# STRWL-S01-V00-Master.net
KiCad netlist of a schematic drawn in Altium Designer
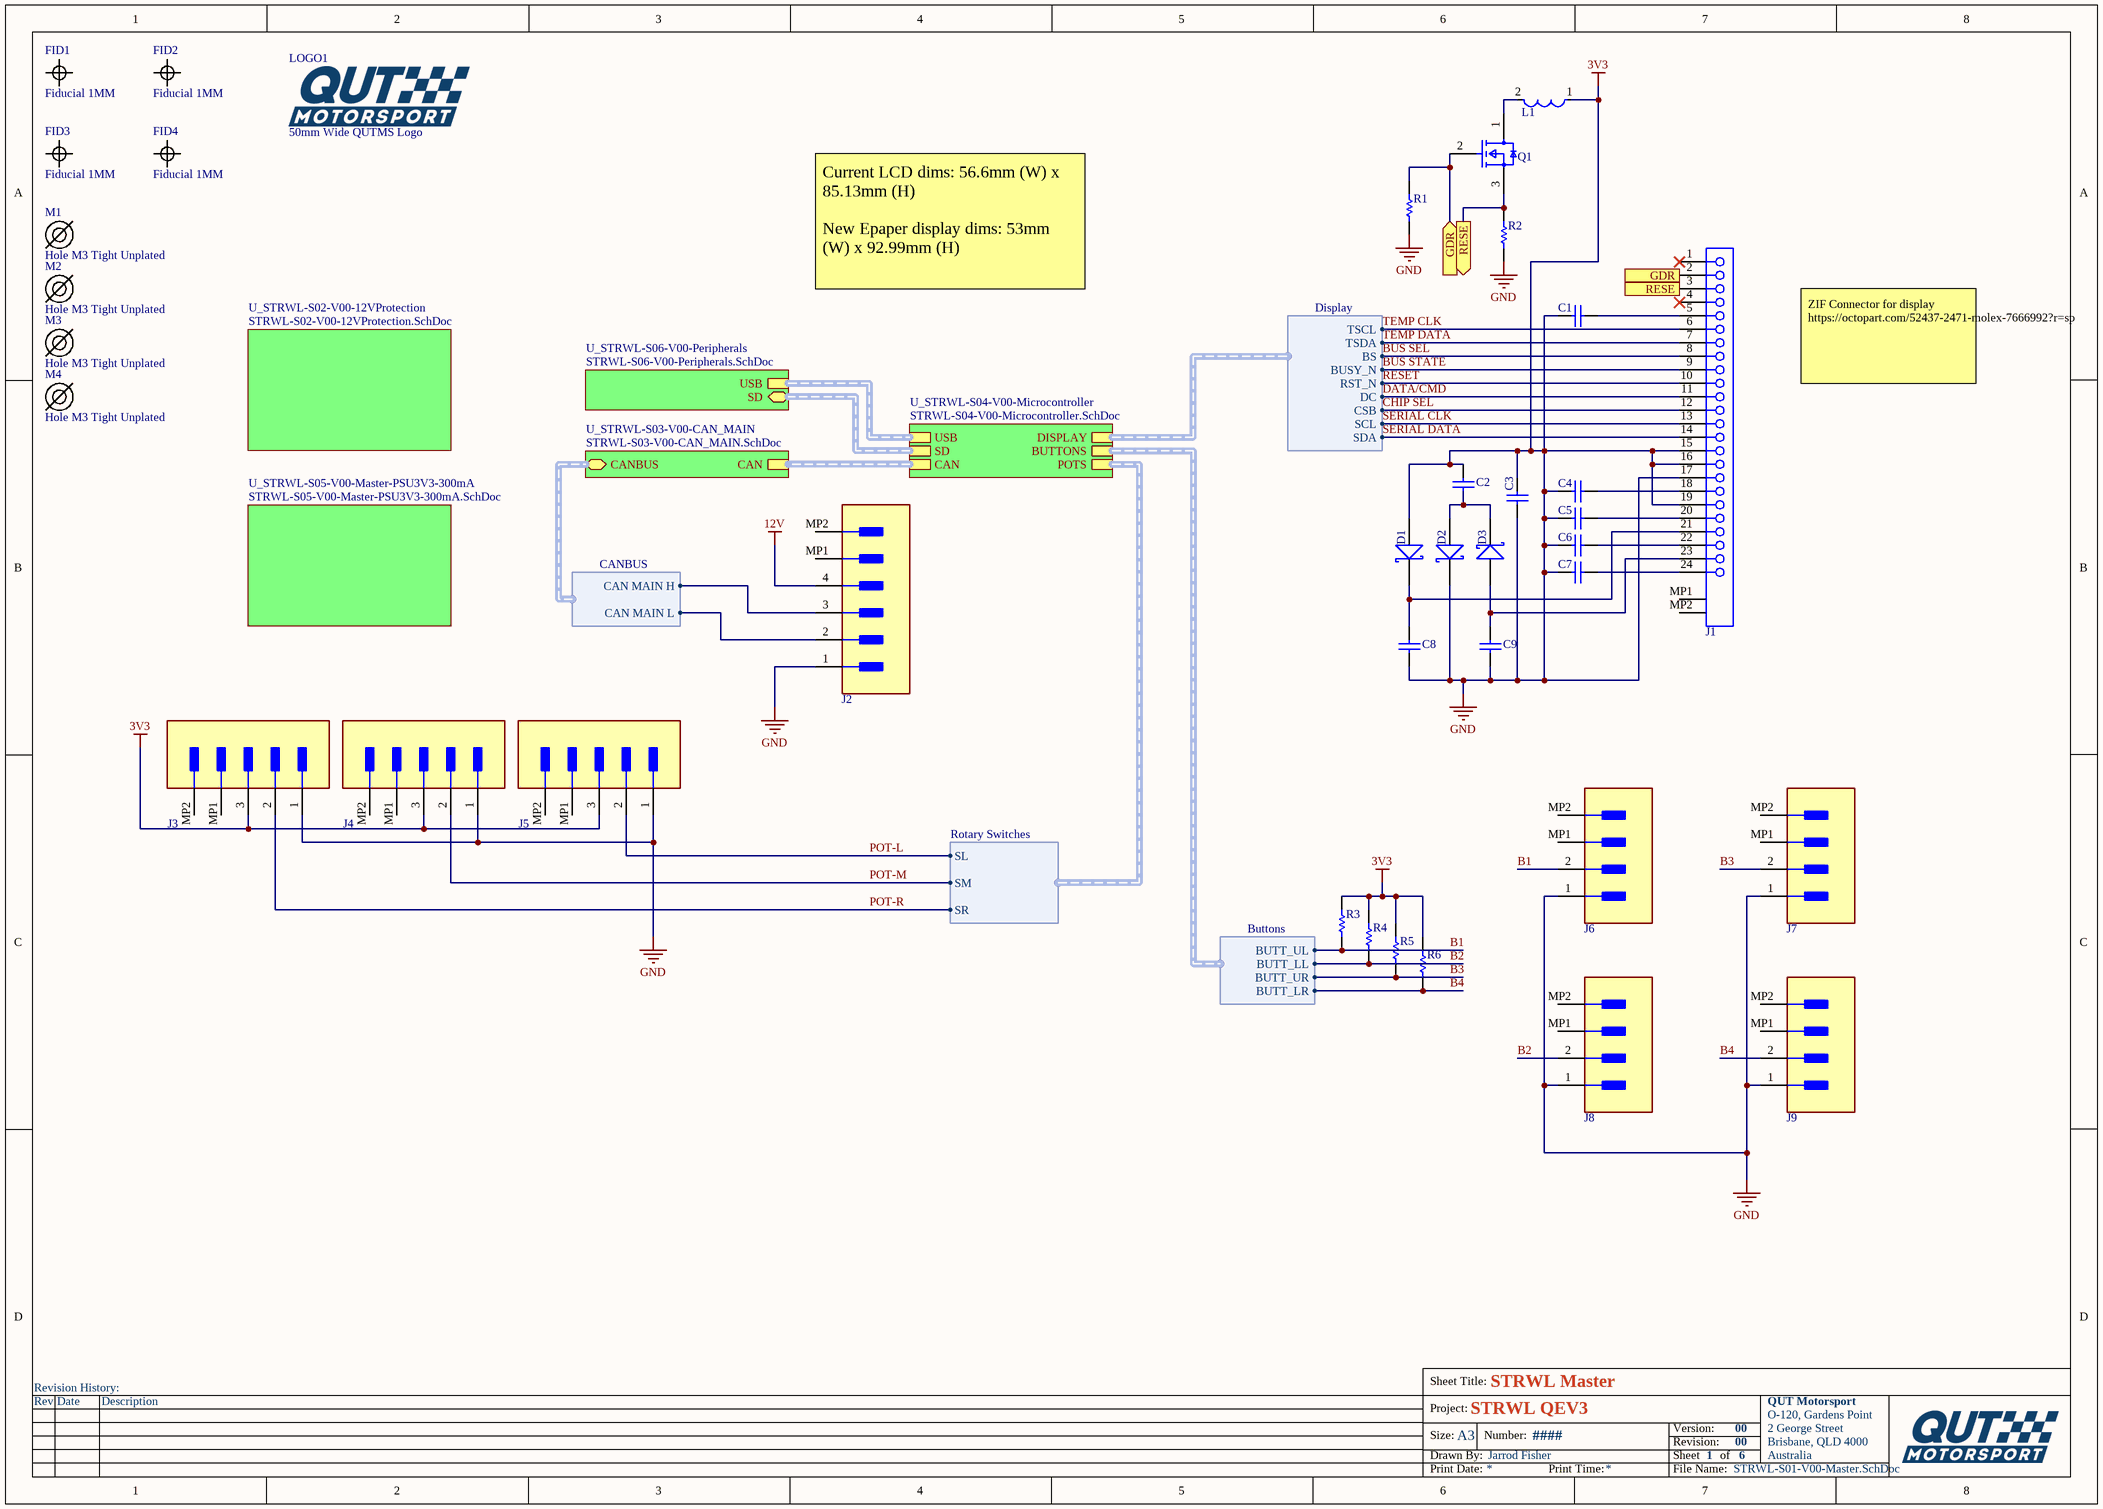
[diagram p0: STRWL-S01-V00-Master.SchDoc]

(export (version "E")
  (design (tool "Eeschema 10.0.6"))
  (components
    (comp (ref "C1")
      (value "1uF 25V 5% X7R 0603")
      (footprint "Cap_Ceramic_0603")
      (description "Capacitor, Ceramic, SMD, 1uF, 25V, 5%, X7R, 0603")
      (libsource (lib "StandardCapacitors") (part "1uF 25V 5% X7R 0603"))
    )
    (comp (ref "C2")
      (value "4u7 50V 5% X7R 0603")
      (footprint "Cap_Ceramic_0603")
      (description "Capacitor, Ceramic, SMD, 4u7, 50V, 5%, X7R, 0603")
      (libsource (lib "StandardCapacitors") (part "4u7 50V 5% X7R 0603"))
    )
    (comp (ref "C3")
      (value "1uF 25V 5% X7R 0603")
      (footprint "Cap_Ceramic_0603")
      (description "Capacitor, Ceramic, SMD, 1uF, 25V, 5%, X7R, 0603")
      (libsource (lib "StandardCapacitors") (part "1uF 25V 5% X7R 0603"))
    )
    (comp (ref "C4")
      (value "1uF 25V 5% X7R 0603")
      (footprint "Cap_Ceramic_0603")
      (description "Capacitor, Ceramic, SMD, 1uF, 25V, 5%, X7R, 0603")
      (libsource (lib "StandardCapacitors") (part "1uF 25V 5% X7R 0603"))
    )
    (comp (ref "C5")
      (value "1uF 25V 5% X7R 0603")
      (footprint "Cap_Ceramic_0603")
      (description "Capacitor, Ceramic, SMD, 1uF, 25V, 5%, X7R, 0603")
      (libsource (lib "StandardCapacitors") (part "1uF 25V 5% X7R 0603"))
    )
    (comp (ref "C6")
      (value "1uF 25V 5% X7R 0603")
      (footprint "Cap_Ceramic_0603")
      (description "Capacitor, Ceramic, SMD, 1uF, 25V, 5%, X7R, 0603")
      (libsource (lib "StandardCapacitors") (part "1uF 25V 5% X7R 0603"))
    )
    (comp (ref "C7")
      (value "1uF 25V 5% X7R 0603")
      (footprint "Cap_Ceramic_0603")
      (description "Capacitor, Ceramic, SMD, 1uF, 25V, 5%, X7R, 0603")
      (libsource (lib "StandardCapacitors") (part "1uF 25V 5% X7R 0603"))
    )
    (comp (ref "C8")
      (value "1uF 25V 5% X7R 0603")
      (footprint "Cap_Ceramic_0603")
      (description "Capacitor, Ceramic, SMD, 1uF, 25V, 5%, X7R, 0603")
      (libsource (lib "StandardCapacitors") (part "1uF 25V 5% X7R 0603"))
    )
    (comp (ref "C9")
      (value "1uF 25V 5% X7R 0603")
      (footprint "Cap_Ceramic_0603")
      (description "Capacitor, Ceramic, SMD, 1uF, 25V, 5%, X7R, 0603")
      (libsource (lib "StandardCapacitors") (part "1uF 25V 5% X7R 0603"))
    )
    (comp (ref "D1")
      (value "STPS0530Z")
      (footprint "SOD123")
      (description "Diode, Schottky Barrier Rectifier, 30 V, 0.5 A, STPS0530Z")
      (libsource (lib "QUTMS_DiodeLibrary") (part "STPS0530Z"))
    )
    (comp (ref "D2")
      (value "STPS0530Z")
      (footprint "SOD123")
      (description "Diode, Schottky Barrier Rectifier, 30 V, 0.5 A, STPS0530Z")
      (libsource (lib "QUTMS_DiodeLibrary") (part "STPS0530Z"))
    )
    (comp (ref "D3")
      (value "STPS0530Z")
      (footprint "SOD123")
      (description "Diode, Schottky Barrier Rectifier, 30 V, 0.5 A, STPS0530Z")
      (libsource (lib "QUTMS_DiodeLibrary") (part "STPS0530Z"))
    )
    (comp (ref "FID1")
      (value "Fiducial 1MM")
      (footprint "FIDUCIAL 1MM")
      (libsource (lib "QUTMS-MCISOLibrary") (part "Fiducial 1MM"))
    )
    (comp (ref "FID2")
      (value "Fiducial 1MM")
      (footprint "FIDUCIAL 1MM")
      (libsource (lib "QUTMS-MCISOLibrary") (part "Fiducial 1MM"))
    )
    (comp (ref "FID3")
      (value "Fiducial 1MM")
      (footprint "FIDUCIAL 1MM")
      (libsource (lib "QUTMS-MCISOLibrary") (part "Fiducial 1MM"))
    )
    (comp (ref "FID4")
      (value "Fiducial 1MM")
      (footprint "FIDUCIAL 1MM")
      (libsource (lib "QUTMS-MCISOLibrary") (part "Fiducial 1MM"))
    )
    (comp (ref "J1")
      (value "52437-2471")
      (footprint "MOLX-52437-2471")
      (fields (field (name "MANUFACTURER") "Molex"))
      (libsource (lib "Molex_52437_2471") (part "52437-2471"))
    )
    (comp (ref "J2")
      (value "JST PH 4 Way VERT SMD")
      (libsource (lib "QUTMS_JSTHeaderLibrary") (part "JST PH 4 Way VERT SMD"))
    )
    (comp (ref "J3")
      (value "JST PH 3 Way VERT SMD")
      (libsource (lib "QUTMS_JSTHeaderLibrary") (part "JST PH 3 Way VERT SMD"))
    )
    (comp (ref "J4")
      (value "JST PH 3 Way VERT SMD")
      (libsource (lib "QUTMS_JSTHeaderLibrary") (part "JST PH 3 Way VERT SMD"))
    )
    (comp (ref "J5")
      (value "JST PH 3 Way VERT SMD")
      (libsource (lib "QUTMS_JSTHeaderLibrary") (part "JST PH 3 Way VERT SMD"))
    )
    (comp (ref "J6")
      (value "JSP PH 2 Way VERT SMD")
      (footprint "JST_B2B-PH-SM4-TB_LF_SN_0")
      (fields (field (name "MANUFACTURER") "JST") (field (name "DIGIKEY PART NUMBER") "455-1734-1-ND"))
      (libsource (lib "QUTMS_JSTHeaderLibrary") (part "JSP PH 2 Way VERT SMD"))
    )
    (comp (ref "J7")
      (value "JSP PH 2 Way VERT SMD")
      (footprint "JST_B2B-PH-SM4-TB_LF_SN_0")
      (fields (field (name "MANUFACTURER") "JST") (field (name "DIGIKEY PART NUMBER") "455-1734-1-ND"))
      (libsource (lib "QUTMS_JSTHeaderLibrary") (part "JSP PH 2 Way VERT SMD"))
    )
    (comp (ref "J8")
      (value "JSP PH 2 Way VERT SMD")
      (footprint "JST_B2B-PH-SM4-TB_LF_SN_0")
      (fields (field (name "MANUFACTURER") "JST") (field (name "DIGIKEY PART NUMBER") "455-1734-1-ND"))
      (libsource (lib "QUTMS_JSTHeaderLibrary") (part "JSP PH 2 Way VERT SMD"))
    )
    (comp (ref "J9")
      (value "JSP PH 2 Way VERT SMD")
      (footprint "JST_B2B-PH-SM4-TB_LF_SN_0")
      (fields (field (name "MANUFACTURER") "JST") (field (name "DIGIKEY PART NUMBER") "455-1734-1-ND"))
      (libsource (lib "QUTMS_JSTHeaderLibrary") (part "JSP PH 2 Way VERT SMD"))
    )
    (comp (ref "L1")
      (value "LQM21FN100M70L")
      (footprint "Murata_LQM21FN_70_IPC_C")
      (libsource (lib "QUTMS_InductorLibrary") (part "LQM21FN100M70L"))
    )
    (comp (ref "LOGO1")
      (value "50mm Wide QUTMS Logo")
      (footprint "QUTMS LOGO 10MM")
      (libsource (lib "QUTMS-MCISOLibrary") (part "QUTMS Logo 50mm"))
    )
    (comp (ref "M1")
      (value "Hole M3 Tight Unplated")
      (footprint "M3.2 UNPLATED")
      (description "M3.2 Hole, No Plating")
      (libsource (lib "QUTMS-MCISOLibrary") (part "Hole M3 Tight Unplated"))
    )
    (comp (ref "M2")
      (value "Hole M3 Tight Unplated")
      (footprint "M3.2 UNPLATED")
      (description "M3.2 Hole, No Plating")
      (libsource (lib "QUTMS-MCISOLibrary") (part "Hole M3 Tight Unplated"))
    )
    (comp (ref "M3")
      (value "Hole M3 Tight Unplated")
      (footprint "M3.2 UNPLATED")
      (description "M3.2 Hole, No Plating")
      (libsource (lib "QUTMS-MCISOLibrary") (part "Hole M3 Tight Unplated"))
    )
    (comp (ref "M4")
      (value "Hole M3 Tight Unplated")
      (footprint "M3.2 UNPLATED")
      (description "M3.2 Hole, No Plating")
      (libsource (lib "QUTMS-MCISOLibrary") (part "Hole M3 Tight Unplated"))
    )
    (comp (ref "Q1")
      (value "MOSFET N-CH 30V 4A SOT323")
      (footprint "Diodes_SOT323_0")
      (description "N-Channel 30V 4A (Ta) 770mW (Ta) Surface Mount SOT-323")
      (libsource (lib "QUTMS_DiodeLibrary") (part "DMN3065LW-13"))
    )
    (comp (ref "R1")
      (value "10k 1% 0603")
      (footprint "Res_ThinFilm_0603")
      (description "Resistor, SMD, 10k, 0.1W, 1%, 0603")
      (libsource (lib "StandardResistors") (part "10k 1% 0603"))
    )
    (comp (ref "R2")
      (value "0R47 5% 0603")
      (footprint "Res_ThinFilm_0603")
      (description "Resistor, SMD, 0R, 0.1W, 5%, 0603")
      (libsource (lib "StandardResistors") (part "0R47 5% 0603_1"))
    )
    (comp (ref "R3")
      (value "10k 5% 0603")
      (footprint "Res_ThinFilm_0603")
      (description "Resistor, SMD, 10k, 0.1W, 5%, 0603")
      (libsource (lib "StandardResistors") (part "10k 5% 0603"))
    )
    (comp (ref "R4")
      (value "10k 5% 0603")
      (footprint "Res_ThinFilm_0603")
      (description "Resistor, SMD, 10k, 0.1W, 5%, 0603")
      (libsource (lib "StandardResistors") (part "10k 5% 0603"))
    )
    (comp (ref "R5")
      (value "10k 5% 0603")
      (footprint "Res_ThinFilm_0603")
      (description "Resistor, SMD, 10k, 0.1W, 5%, 0603")
      (libsource (lib "StandardResistors") (part "10k 5% 0603"))
    )
    (comp (ref "R6")
      (value "10k 5% 0603")
      (footprint "Res_ThinFilm_0603")
      (description "Resistor, SMD, 10k, 0.1W, 5%, 0603")
      (libsource (lib "StandardResistors") (part "10k 5% 0603"))
    )
  )
  (nets
    (net (code "6") (name "/B1") (class "Default")
      (node (ref "J6") (pin "2") (pinfunction "2_2") (pintype "passive"))
      (node (ref "R3") (pin "2") (pinfunction "2_2") (pintype "passive"))
    )
    (net (code "7") (name "/B2") (class "Default")
      (node (ref "J8") (pin "2") (pinfunction "2_2") (pintype "passive"))
      (node (ref "R4") (pin "2") (pinfunction "2_2") (pintype "passive"))
    )
    (net (code "8") (name "/B3") (class "Default")
      (node (ref "J7") (pin "2") (pinfunction "2_2") (pintype "passive"))
      (node (ref "R5") (pin "1") (pinfunction "1_1") (pintype "passive"))
    )
    (net (code "9") (name "/B4") (class "Default")
      (node (ref "J9") (pin "2") (pinfunction "2_2") (pintype "passive"))
      (node (ref "R6") (pin "1") (pinfunction "1_1") (pintype "passive"))
    )
    (net (code "10") (name "/BUS SEL") (class "Default")
      (node (ref "J1") (pin "8") (pinfunction "8_8") (pintype "passive"))
    )
    (net (code "11") (name "/BUS STATE") (class "Default")
      (node (ref "J1") (pin "9") (pinfunction "9_9") (pintype "passive"))
    )
    (net (code "12") (name "/CAN MAIN H") (class "Default")
      (node (ref "J2") (pin "3") (pinfunction "3_3") (pintype "passive"))
    )
    (net (code "13") (name "/CAN MAIN L") (class "Default")
      (node (ref "J2") (pin "2") (pinfunction "2_2") (pintype "passive"))
    )
    (net (code "15") (name "/CHIP SEL") (class "Default")
      (node (ref "J1") (pin "12") (pinfunction "12_12") (pintype "passive"))
    )
    (net (code "16") (name "/DATA{slash}CMD") (class "Default")
      (node (ref "J1") (pin "11") (pinfunction "11_11") (pintype "passive"))
    )
    (net (code "17") (name "/GDR") (class "Default")
      (node (ref "J1") (pin "2") (pinfunction "2_2") (pintype "passive"))
      (node (ref "Q1") (pin "2") (pinfunction "G_2") (pintype "passive"))
      (node (ref "R1") (pin "1") (pinfunction "1_1") (pintype "passive"))
    )
    (net (code "18") (name "/POT-L") (class "Default")
      (node (ref "J5") (pin "2") (pinfunction "2_2") (pintype "passive"))
    )
    (net (code "19") (name "/POT-M") (class "Default")
      (node (ref "J4") (pin "2") (pinfunction "2_2") (pintype "passive"))
    )
    (net (code "20") (name "/POT-R") (class "Default")
      (node (ref "J3") (pin "2") (pinfunction "2_2") (pintype "passive"))
    )
    (net (code "21") (name "/RESE") (class "Default")
      (node (ref "J1") (pin "3") (pinfunction "3_3") (pintype "passive"))
      (node (ref "Q1") (pin "3") (pinfunction "S_3") (pintype "passive"))
      (node (ref "R2") (pin "2") (pinfunction "2_2") (pintype "passive"))
    )
    (net (code "22") (name "/RESET") (class "Default")
      (node (ref "J1") (pin "10") (pinfunction "10_10") (pintype "passive"))
    )
    (net (code "24") (name "/SERIAL CLK") (class "Default")
      (node (ref "J1") (pin "13") (pinfunction "13_13") (pintype "passive"))
    )
    (net (code "25") (name "/SERIAL DATA") (class "Default")
      (node (ref "J1") (pin "14") (pinfunction "14_14") (pintype "passive"))
    )
    (net (code "26") (name "/TEMP CLK") (class "Default")
      (node (ref "J1") (pin "6") (pinfunction "6_6") (pintype "passive"))
    )
    (net (code "27") (name "/TEMP DATA") (class "Default")
      (node (ref "J1") (pin "7") (pinfunction "7_7") (pintype "passive"))
    )
    (net (code "33") (name "3V3") (class "Default")
      (node (ref "C1") (pin "1") (pinfunction "1_1") (pintype "passive"))
      (node (ref "C2") (pin "2") (pinfunction "2_2") (pintype "passive"))
      (node (ref "C3") (pin "1") (pinfunction "1_1") (pintype "passive"))
      (node (ref "C3") (pin "2") (pinfunction "2_2") (pintype "passive"))
      (node (ref "C4") (pin "1") (pinfunction "1_1") (pintype "passive"))
      (node (ref "C5") (pin "1") (pinfunction "1_1") (pintype "passive"))
      (node (ref "C6") (pin "1") (pinfunction "1_1") (pintype "passive"))
      (node (ref "C7") (pin "1") (pinfunction "1_1") (pintype "passive"))
      (node (ref "C8") (pin "1") (pinfunction "1_1") (pintype "passive"))
      (node (ref "C9") (pin "1") (pinfunction "1_1") (pintype "passive"))
      (node (ref "D1") (pin "A") (pinfunction "A_A") (pintype "passive"))
      (node (ref "D2") (pin "K") (pinfunction "K_K") (pintype "passive"))
      (node (ref "J1") (pin "15") (pinfunction "15_15") (pintype "passive"))
      (node (ref "J1") (pin "16") (pinfunction "16_16") (pintype "passive"))
      (node (ref "J1") (pin "17") (pinfunction "17_17") (pintype "passive"))
      (node (ref "J1") (pin "19") (pinfunction "19_19") (pintype "passive"))
      (node (ref "J2") (pin "1") (pinfunction "1_1") (pintype "passive"))
      (node (ref "J3") (pin "1") (pinfunction "1_1") (pintype "passive"))
      (node (ref "J3") (pin "3") (pinfunction "3_3") (pintype "passive"))
      (node (ref "J4") (pin "1") (pinfunction "1_1") (pintype "passive"))
      (node (ref "J4") (pin "3") (pinfunction "3_3") (pintype "passive"))
      (node (ref "J5") (pin "1") (pinfunction "1_1") (pintype "passive"))
      (node (ref "J5") (pin "3") (pinfunction "3_3") (pintype "passive"))
      (node (ref "J6") (pin "1") (pinfunction "1_1") (pintype "passive"))
      (node (ref "J7") (pin "1") (pinfunction "1_1") (pintype "passive"))
      (node (ref "J8") (pin "1") (pinfunction "1_1") (pintype "passive"))
      (node (ref "J9") (pin "1") (pinfunction "1_1") (pintype "passive"))
      (node (ref "L1") (pin "1") (pinfunction "1_1") (pintype "passive"))
      (node (ref "R1") (pin "2") (pinfunction "2_2") (pintype "passive"))
      (node (ref "R2") (pin "1") (pinfunction "1_1") (pintype "passive"))
      (node (ref "R3") (pin "1") (pinfunction "1_1") (pintype "passive"))
      (node (ref "R4") (pin "1") (pinfunction "1_1") (pintype "passive"))
      (node (ref "R5") (pin "2") (pinfunction "2_2") (pintype "passive"))
      (node (ref "R6") (pin "2") (pinfunction "2_2") (pintype "passive"))
    )
    (net (code "34") (name "12V") (class "Default")
      (node (ref "J2") (pin "4") (pinfunction "4_4") (pintype "passive"))
    )
    (net (code "35") (name "Net-(C1-Pad2)") (class "Default")
      (node (ref "C1") (pin "2") (pinfunction "2_2") (pintype "passive"))
      (node (ref "J1") (pin "5") (pinfunction "5_5") (pintype "passive"))
    )
    (net (code "36") (name "Net-(C2-Pad1)") (class "Default")
      (node (ref "C2") (pin "1") (pinfunction "1_1") (pintype "passive"))
      (node (ref "D2") (pin "A") (pinfunction "A_A") (pintype "passive"))
      (node (ref "D3") (pin "K") (pinfunction "K_K") (pintype "passive"))
    )
    (net (code "37") (name "Net-(C4-Pad2)") (class "Default")
      (node (ref "C4") (pin "2") (pinfunction "2_2") (pintype "passive"))
      (node (ref "J1") (pin "18") (pinfunction "18_18") (pintype "passive"))
    )
    (net (code "38") (name "Net-(C5-Pad2)") (class "Default")
      (node (ref "C5") (pin "2") (pinfunction "2_2") (pintype "passive"))
      (node (ref "J1") (pin "20") (pinfunction "20_20") (pintype "passive"))
    )
    (net (code "39") (name "Net-(C6-Pad2)") (class "Default")
      (node (ref "C6") (pin "2") (pinfunction "2_2") (pintype "passive"))
      (node (ref "J1") (pin "22") (pinfunction "22_22") (pintype "passive"))
    )
    (net (code "40") (name "Net-(C7-Pad2)") (class "Default")
      (node (ref "C7") (pin "2") (pinfunction "2_2") (pintype "passive"))
      (node (ref "J1") (pin "24") (pinfunction "24_24") (pintype "passive"))
    )
    (net (code "41") (name "Net-(C8-Pad2)") (class "Default")
      (node (ref "C8") (pin "2") (pinfunction "2_2") (pintype "passive"))
      (node (ref "D1") (pin "K") (pinfunction "K_K") (pintype "passive"))
      (node (ref "J1") (pin "21") (pinfunction "21_21") (pintype "passive"))
    )
    (net (code "42") (name "Net-(C9-Pad2)") (class "Default")
      (node (ref "C9") (pin "2") (pinfunction "2_2") (pintype "passive"))
      (node (ref "D3") (pin "A") (pinfunction "A_A") (pintype "passive"))
      (node (ref "J1") (pin "23") (pinfunction "23_23") (pintype "passive"))
    )
    (net (code "43") (name "Net-(Q1-D)") (class "Default")
      (node (ref "L1") (pin "2") (pinfunction "2_2") (pintype "passive"))
      (node (ref "Q1") (pin "1") (pinfunction "D_1") (pintype "passive"))
    )
    (net (code "44") (name "unconnected-(J1-Pad1)") (class "Default")
      (node (ref "J1") (pin "1") (pinfunction "1_1") (pintype "passive+no_connect"))
    )
    (net (code "45") (name "unconnected-(J1-Pad4)") (class "Default")
      (node (ref "J1") (pin "4") (pinfunction "4_4") (pintype "passive+no_connect"))
    )
    (net (code "46") (name "unconnected-(J1-PadMP1)") (class "Default")
      (node (ref "J1") (pin "MP1") (pinfunction "MP1_MP1") (pintype "passive"))
    )
    (net (code "47") (name "unconnected-(J1-PadMP2)") (class "Default")
      (node (ref "J1") (pin "MP2") (pinfunction "MP2_MP2") (pintype "passive"))
    )
    (net (code "48") (name "unconnected-(J2-MNT_1-PadMP1)") (class "Default")
      (node (ref "J2") (pin "MP1") (pinfunction "MNT_1_MP1") (pintype "passive"))
    )
    (net (code "49") (name "unconnected-(J2-MNT_2-PadMP2)") (class "Default")
      (node (ref "J2") (pin "MP2") (pinfunction "MNT_2_MP2") (pintype "passive"))
    )
    (net (code "50") (name "unconnected-(J3-MNT_1-PadMP1)") (class "Default")
      (node (ref "J3") (pin "MP1") (pinfunction "MNT_1_MP1") (pintype "passive"))
    )
    (net (code "51") (name "unconnected-(J3-MNT_2-PadMP2)") (class "Default")
      (node (ref "J3") (pin "MP2") (pinfunction "MNT_2_MP2") (pintype "passive"))
    )
    (net (code "52") (name "unconnected-(J4-MNT_1-PadMP1)") (class "Default")
      (node (ref "J4") (pin "MP1") (pinfunction "MNT_1_MP1") (pintype "passive"))
    )
    (net (code "53") (name "unconnected-(J4-MNT_2-PadMP2)") (class "Default")
      (node (ref "J4") (pin "MP2") (pinfunction "MNT_2_MP2") (pintype "passive"))
    )
    (net (code "54") (name "unconnected-(J5-MNT_1-PadMP1)") (class "Default")
      (node (ref "J5") (pin "MP1") (pinfunction "MNT_1_MP1") (pintype "passive"))
    )
    (net (code "55") (name "unconnected-(J5-MNT_2-PadMP2)") (class "Default")
      (node (ref "J5") (pin "MP2") (pinfunction "MNT_2_MP2") (pintype "passive"))
    )
    (net (code "56") (name "unconnected-(J6-MNT_1-PadMP1)") (class "Default")
      (node (ref "J6") (pin "MP1") (pinfunction "MNT_1_MP1") (pintype "passive"))
    )
    (net (code "57") (name "unconnected-(J6-MNT_2-PadMP2)") (class "Default")
      (node (ref "J6") (pin "MP2") (pinfunction "MNT_2_MP2") (pintype "passive"))
    )
    (net (code "58") (name "unconnected-(J7-MNT_1-PadMP1)") (class "Default")
      (node (ref "J7") (pin "MP1") (pinfunction "MNT_1_MP1") (pintype "passive"))
    )
    (net (code "59") (name "unconnected-(J7-MNT_2-PadMP2)") (class "Default")
      (node (ref "J7") (pin "MP2") (pinfunction "MNT_2_MP2") (pintype "passive"))
    )
    (net (code "60") (name "unconnected-(J8-MNT_1-PadMP1)") (class "Default")
      (node (ref "J8") (pin "MP1") (pinfunction "MNT_1_MP1") (pintype "passive"))
    )
    (net (code "61") (name "unconnected-(J8-MNT_2-PadMP2)") (class "Default")
      (node (ref "J8") (pin "MP2") (pinfunction "MNT_2_MP2") (pintype "passive"))
    )
    (net (code "62") (name "unconnected-(J9-MNT_1-PadMP1)") (class "Default")
      (node (ref "J9") (pin "MP1") (pinfunction "MNT_1_MP1") (pintype "passive"))
    )
    (net (code "63") (name "unconnected-(J9-MNT_2-PadMP2)") (class "Default")
      (node (ref "J9") (pin "MP2") (pinfunction "MNT_2_MP2") (pintype "passive"))
    )
  )
)
